# sht75_sensorion_board.net
KiCad netlist of a schematic drawn in Altium Designer
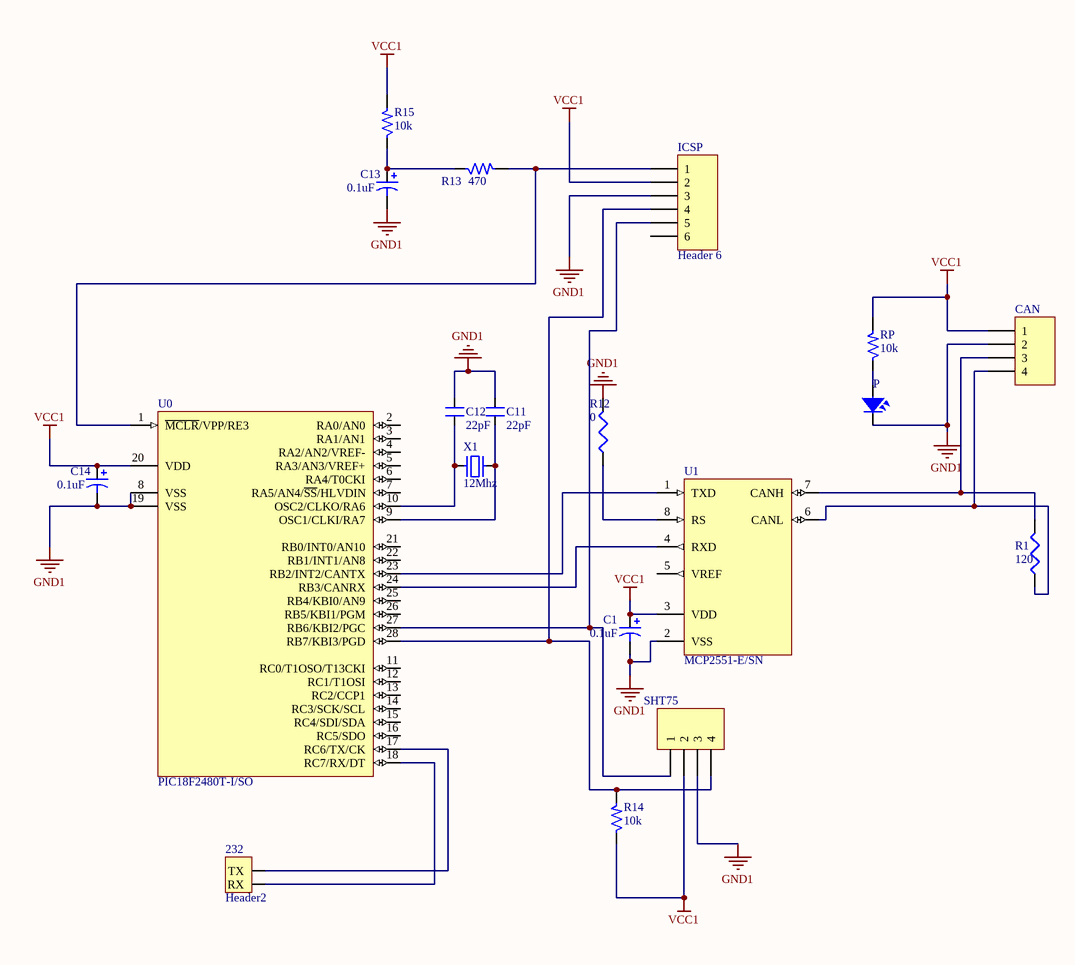
[diagram p0: sht75_sensorion_board.SchDoc]

(export (version "E")
  (design (tool "Eeschema 10.0.6"))
  (components
    (comp (ref "232")
      (value "Header2")
      (footprint "HDR2")
      (description "Header IDC, 2 x 1 Pin Vertical 2.54mm Pitch (Non-Boxed, Male)")
      (fields
        (field (name "MANUFACTURER") "Würth Elektronik eiSos GmbH")
        (field (name "PARTNO") "613002143121")
        (field (name "CREATED BY") "Karrer Zheng")
      )
      (libsource (lib "LIBRARY") (part "Header2"))
    )
    (comp (ref "C1")
      (value "0.1uF")
      (footprint "C0805")
      (description "Polarized Capacitor (Surface Mount)")
      (fields (field (name "Comment") "Cap Pol3") (field (name "PUBLISHER") "Altium Limited"))
      (libsource (lib "Miscellaneous Devices") (part "Cap Pol3"))
    )
    (comp (ref "C11")
      (value "22pF")
      (footprint "CN1")
      (description "Cremic For Xtal 1pF => 100pF")
      (libsource (lib "electronicvn-library1") (part "CN0"))
    )
    (comp (ref "C12")
      (value "22pF")
      (footprint "CN1")
      (description "Cremic For Xtal 1pF => 100pF")
      (libsource (lib "electronicvn-library1") (part "CN0"))
    )
    (comp (ref "C13")
      (value "0.1uF")
      (footprint "C0805")
      (description "Polarized Capacitor (Surface Mount)")
      (fields (field (name "Comment") "Cap Pol3") (field (name "PUBLISHER") "Altium Limited"))
      (libsource (lib "Miscellaneous Devices") (part "Cap Pol3"))
    )
    (comp (ref "C14")
      (value "0.1uF")
      (footprint "C0805")
      (description "Polarized Capacitor (Surface Mount)")
      (fields (field (name "Comment") "Cap Pol3") (field (name "PUBLISHER") "Altium Limited"))
      (libsource (lib "Miscellaneous Devices") (part "Cap Pol3"))
    )
    (comp (ref "CAN")
      (value "Header 4")
      (footprint "HDR1X4")
      (description "Header, 4-Pin")
      (fields (field (name "PUBLISHER") "Altium Limited"))
      (libsource (lib "Miscellaneous Connectors") (part "Header 4"))
    )
    (comp (ref "ICSP")
      (value "Header 6")
      (footprint "HDR1X6")
      (description "Header, 6-Pin")
      (fields (field (name "PUBLISHER") "Altium Limited"))
      (libsource (lib "Miscellaneous Connectors") (part "Header 6"))
    )
    (comp (ref "P")
      (value "LED")
      (footprint "LED-3MM-YELLOW")
      (description "LED Single colour Green and Red")
      (libsource (lib "LIBRARY") (part "LED"))
    )
    (comp (ref "R1")
      (value "120")
      (footprint "J1-0603")
      (description "Resistor")
      (fields (field (name "Comment") "Res3") (field (name "PUBLISHER") "Altium Limited"))
      (libsource (lib "Miscellaneous Devices") (part "Res3"))
    )
    (comp (ref "R12")
      (value "0")
      (footprint "J1-0603")
      (description "Resistor")
      (fields (field (name "Comment") "Res3") (field (name "PUBLISHER") "Altium Limited"))
      (libsource (lib "Miscellaneous Devices") (part "Res3"))
    )
    (comp (ref "R13")
      (value "470")
      (footprint "SM-RES-1206")
      (description "Resistor 1/4W")
      (libsource (lib "electronicvn-library1") (part "R"))
    )
    (comp (ref "R14")
      (value "10k")
      (footprint "RES-SMD-1206")
      (description "Resistor 1/4W")
      (libsource (lib "electronicvn-library1") (part "R"))
    )
    (comp (ref "R15")
      (value "10k")
      (footprint "SM-RES-1206")
      (description "Resistor 1/4W")
      (libsource (lib "electronicvn-library1") (part "R"))
    )
    (comp (ref "RP")
      (value "10k")
      (footprint "SM-RES-1206")
      (description "Resistor 1/4W")
      (libsource (lib "electronicvn-library1") (part "R"))
    )
    (comp (ref "SHT75")
      (value "Header 4")
      (footprint "HDR1X4")
      (description "Header, 4-Pin")
      (fields (field (name "PUBLISHER") "Altium Limited"))
      (libsource (lib "") (part "Header 4_1"))
    )
    (comp (ref "U0")
      (value "PIC18F2480T-I/SO")
      (footprint "SOIC-SO28_L")
      (fields (field (name "PUBLISHER") "Altium Limited"))
      (libsource (lib "Microchip Microcontroller 8-Bit PIC18") (part "PIC18F2480T-I/SO"))
    )
    (comp (ref "U1")
      (value "MCP2551-E/SN")
      (footprint "SOIC-SN8_N")
      (description "High-Speed CAN Transceiver, 8-Pin SOIC, Extended Temperature")
      (fields (field (name "PUBLISHER") "Altium Limited"))
      (libsource (lib "Microchip Interface") (part "MCP2551-E/SN"))
    )
    (comp (ref "X1")
      (value "12Mhz")
      (footprint "XT2")
      (description "Crystal, 32.768 KHz, -40 to 85 degC, 3.2 x 1.5 x 0.9 mm SMD")
      (libsource (lib "LIBRARY") (part "XT2"))
    )
  )
  (nets
    (net (code "1") (name "GND1") (class "Default")
      (node (ref "C1") (pin "2") (pinfunction "2_2") (pintype "passive"))
      (node (ref "C11") (pin "2") (pinfunction "2_2") (pintype "passive"))
      (node (ref "C12") (pin "2") (pinfunction "2_2") (pintype "passive"))
      (node (ref "C13") (pin "2") (pinfunction "2_2") (pintype "passive"))
      (node (ref "C14") (pin "2") (pinfunction "2_2") (pintype "passive"))
      (node (ref "CAN") (pin "2") (pinfunction "2_2") (pintype "passive"))
      (node (ref "ICSP") (pin "3") (pinfunction "3_3") (pintype "passive"))
      (node (ref "P") (pin "2") (pinfunction "2_2") (pintype "passive"))
      (node (ref "R12") (pin "2") (pinfunction "2_2") (pintype "passive"))
      (node (ref "SHT75") (pin "3") (pinfunction "3_3") (pintype "passive"))
      (node (ref "U0") (pin "19") (pinfunction "VSS_19") (pintype "power_in"))
      (node (ref "U0") (pin "8") (pinfunction "VSS_8") (pintype "power_in"))
      (node (ref "U1") (pin "2") (pinfunction "VSS_2") (pintype "power_in"))
    )
    (net (code "2") (name "Net-(232-RX)") (class "Default")
      (node (ref "232") (pin "1") (pinfunction "RX_1") (pintype "passive"))
      (node (ref "U0") (pin "18") (pinfunction "RC7/RX/DT_18") (pintype "bidirectional"))
    )
    (net (code "3") (name "Net-(232-TX)") (class "Default")
      (node (ref "232") (pin "2") (pinfunction "TX_2") (pintype "passive"))
      (node (ref "U0") (pin "17") (pinfunction "RC6/TX/CK_17") (pintype "bidirectional"))
    )
    (net (code "4") (name "Net-(C13-Pad1)") (class "Default")
      (node (ref "C13") (pin "1") (pinfunction "1_1") (pintype "passive"))
      (node (ref "R13") (pin "1") (pinfunction "1_1") (pintype "passive"))
      (node (ref "R15") (pin "1") (pinfunction "1_1") (pintype "passive"))
    )
    (net (code "5") (name "Net-(P-Pad1)") (class "Default")
      (node (ref "P") (pin "1") (pinfunction "1_1") (pintype "passive"))
      (node (ref "RP") (pin "1") (pinfunction "1_1") (pintype "passive"))
    )
    (net (code "6") (name "Net-(U0-OSC1{slash}CLKI{slash}RA7)") (class "Default")
      (node (ref "C11") (pin "1") (pinfunction "1_1") (pintype "passive"))
      (node (ref "U0") (pin "9") (pinfunction "OSC1/CLKI/RA7_9") (pintype "bidirectional"))
      (node (ref "X1") (pin "2") (pinfunction "2_2") (pintype "passive"))
    )
    (net (code "7") (name "Net-(U0-OSC2{slash}CLKO{slash}RA6)") (class "Default")
      (node (ref "C12") (pin "1") (pinfunction "1_1") (pintype "passive"))
      (node (ref "U0") (pin "10") (pinfunction "OSC2/CLKO/RA6_10") (pintype "bidirectional"))
      (node (ref "X1") (pin "1") (pinfunction "1_1") (pintype "passive"))
    )
    (net (code "8") (name "Net-(U0-RB2{slash}INT2{slash}CANTX)") (class "Default")
      (node (ref "U0") (pin "23") (pinfunction "RB2/INT2/CANTX_23") (pintype "bidirectional"))
      (node (ref "U1") (pin "1") (pinfunction "TXD_1") (pintype "input"))
    )
    (net (code "9") (name "Net-(U0-RB3{slash}CANRX)") (class "Default")
      (node (ref "U0") (pin "24") (pinfunction "RB3/CANRX_24") (pintype "bidirectional"))
      (node (ref "U1") (pin "4") (pinfunction "RXD_4") (pintype "output"))
    )
    (net (code "10") (name "Net-(U0-RB6{slash}KBI2{slash}PGC)") (class "Default")
      (node (ref "ICSP") (pin "5") (pinfunction "5_5") (pintype "passive"))
      (node (ref "SHT75") (pin "1") (pinfunction "1_1") (pintype "passive"))
      (node (ref "U0") (pin "27") (pinfunction "RB6/KBI2/PGC_27") (pintype "bidirectional"))
    )
    (net (code "11") (name "Net-(U0-RB7{slash}KBI3{slash}PGD)") (class "Default")
      (node (ref "ICSP") (pin "4") (pinfunction "4_4") (pintype "passive"))
      (node (ref "R14") (pin "2") (pinfunction "2_2") (pintype "passive"))
      (node (ref "SHT75") (pin "4") (pinfunction "4_4") (pintype "passive"))
      (node (ref "U0") (pin "28") (pinfunction "RB7/KBI3/PGD_28") (pintype "bidirectional"))
    )
    (net (code "12") (name "Net-(U0-~{MCLR}{slash}VPP{slash}RE3)") (class "Default")
      (node (ref "ICSP") (pin "1") (pinfunction "1_1") (pintype "passive"))
      (node (ref "R13") (pin "2") (pinfunction "2_2") (pintype "passive"))
      (node (ref "U0") (pin "1") (pinfunction "~{MCLR}/VPP/RE3_1") (pintype "input"))
    )
    (net (code "13") (name "Net-(U1-CANH)") (class "Default")
      (node (ref "CAN") (pin "3") (pinfunction "3_3") (pintype "passive"))
      (node (ref "R1") (pin "2") (pinfunction "2_2") (pintype "passive"))
      (node (ref "U1") (pin "7") (pinfunction "CANH_7") (pintype "bidirectional"))
    )
    (net (code "14") (name "Net-(U1-CANL)") (class "Default")
      (node (ref "CAN") (pin "4") (pinfunction "4_4") (pintype "passive"))
      (node (ref "R1") (pin "1") (pinfunction "1_1") (pintype "passive"))
      (node (ref "U1") (pin "6") (pinfunction "CANL_6") (pintype "bidirectional"))
    )
    (net (code "15") (name "Net-(U1-RS)") (class "Default")
      (node (ref "R12") (pin "1") (pinfunction "1_1") (pintype "passive"))
      (node (ref "U1") (pin "8") (pinfunction "RS_8") (pintype "input"))
    )
    (net (code "16") (name "VCC1") (class "Default")
      (node (ref "C1") (pin "1") (pinfunction "1_1") (pintype "passive"))
      (node (ref "C14") (pin "1") (pinfunction "1_1") (pintype "passive"))
      (node (ref "CAN") (pin "1") (pinfunction "1_1") (pintype "passive"))
      (node (ref "ICSP") (pin "2") (pinfunction "2_2") (pintype "passive"))
      (node (ref "R14") (pin "1") (pinfunction "1_1") (pintype "passive"))
      (node (ref "R15") (pin "2") (pinfunction "2_2") (pintype "passive"))
      (node (ref "RP") (pin "2") (pinfunction "2_2") (pintype "passive"))
      (node (ref "SHT75") (pin "2") (pinfunction "2_2") (pintype "passive"))
      (node (ref "U0") (pin "20") (pinfunction "VDD_20") (pintype "power_in"))
      (node (ref "U1") (pin "3") (pinfunction "VDD_3") (pintype "power_in"))
    )
    (net (code "17") (name "unconnected-(ICSP-Pad6)") (class "Default")
      (node (ref "ICSP") (pin "6") (pinfunction "6_6") (pintype "passive"))
    )
    (net (code "18") (name "unconnected-(U0-RA0{slash}AN0-Pad2)") (class "Default")
      (node (ref "U0") (pin "2") (pinfunction "RA0/AN0_2") (pintype "bidirectional"))
    )
    (net (code "19") (name "unconnected-(U0-RA1{slash}AN1-Pad3)") (class "Default")
      (node (ref "U0") (pin "3") (pinfunction "RA1/AN1_3") (pintype "bidirectional"))
    )
    (net (code "20") (name "unconnected-(U0-RA2{slash}AN2{slash}VREF--Pad4)") (class "Default")
      (node (ref "U0") (pin "4") (pinfunction "RA2/AN2/VREF-_4") (pintype "bidirectional"))
    )
    (net (code "21") (name "unconnected-(U0-RA3{slash}AN3{slash}VREF+-Pad5)") (class "Default")
      (node (ref "U0") (pin "5") (pinfunction "RA3/AN3/VREF+_5") (pintype "bidirectional"))
    )
    (net (code "22") (name "unconnected-(U0-RA4{slash}T0CKI-Pad6)") (class "Default")
      (node (ref "U0") (pin "6") (pinfunction "RA4/T0CKI_6") (pintype "bidirectional"))
    )
    (net (code "23") (name "unconnected-(U0-RA5{slash}AN4{slash}~{SS}{slash}HLVDIN-Pad7)") (class "Default")
      (node (ref "U0") (pin "7") (pinfunction "RA5/AN4/~{SS}/HLVDIN_7") (pintype "bidirectional"))
    )
    (net (code "24") (name "unconnected-(U0-RB0{slash}INT0{slash}AN10-Pad21)") (class "Default")
      (node (ref "U0") (pin "21") (pinfunction "RB0/INT0/AN10_21") (pintype "bidirectional"))
    )
    (net (code "25") (name "unconnected-(U0-RB1{slash}INT1{slash}AN8-Pad22)") (class "Default")
      (node (ref "U0") (pin "22") (pinfunction "RB1/INT1/AN8_22") (pintype "bidirectional"))
    )
    (net (code "26") (name "unconnected-(U0-RB4{slash}KBI0{slash}AN9-Pad25)") (class "Default")
      (node (ref "U0") (pin "25") (pinfunction "RB4/KBI0/AN9_25") (pintype "bidirectional"))
    )
    (net (code "27") (name "unconnected-(U0-RB5{slash}KBI1{slash}PGM-Pad26)") (class "Default")
      (node (ref "U0") (pin "26") (pinfunction "RB5/KBI1/PGM_26") (pintype "bidirectional"))
    )
    (net (code "28") (name "unconnected-(U0-RC0{slash}T1OSO{slash}T13CKI-Pad11)") (class "Default")
      (node (ref "U0") (pin "11") (pinfunction "RC0/T1OSO/T13CKI_11") (pintype "bidirectional"))
    )
    (net (code "29") (name "unconnected-(U0-RC1{slash}T1OSI-Pad12)") (class "Default")
      (node (ref "U0") (pin "12") (pinfunction "RC1/T1OSI_12") (pintype "bidirectional"))
    )
    (net (code "30") (name "unconnected-(U0-RC2{slash}CCP1-Pad13)") (class "Default")
      (node (ref "U0") (pin "13") (pinfunction "RC2/CCP1_13") (pintype "bidirectional"))
    )
    (net (code "31") (name "unconnected-(U0-RC3{slash}SCK{slash}SCL-Pad14)") (class "Default")
      (node (ref "U0") (pin "14") (pinfunction "RC3/SCK/SCL_14") (pintype "bidirectional"))
    )
    (net (code "32") (name "unconnected-(U0-RC4{slash}SDI{slash}SDA-Pad15)") (class "Default")
      (node (ref "U0") (pin "15") (pinfunction "RC4/SDI/SDA_15") (pintype "bidirectional"))
    )
    (net (code "33") (name "unconnected-(U0-RC5{slash}SDO-Pad16)") (class "Default")
      (node (ref "U0") (pin "16") (pinfunction "RC5/SDO_16") (pintype "bidirectional"))
    )
    (net (code "34") (name "unconnected-(U1-VREF-Pad5)") (class "Default")
      (node (ref "U1") (pin "5") (pinfunction "VREF_5") (pintype "output"))
    )
  )
)
